# ProProject__CW32__2024-03-17.net
KiCad netlist of a schematic drawn in EasyEDA Pro
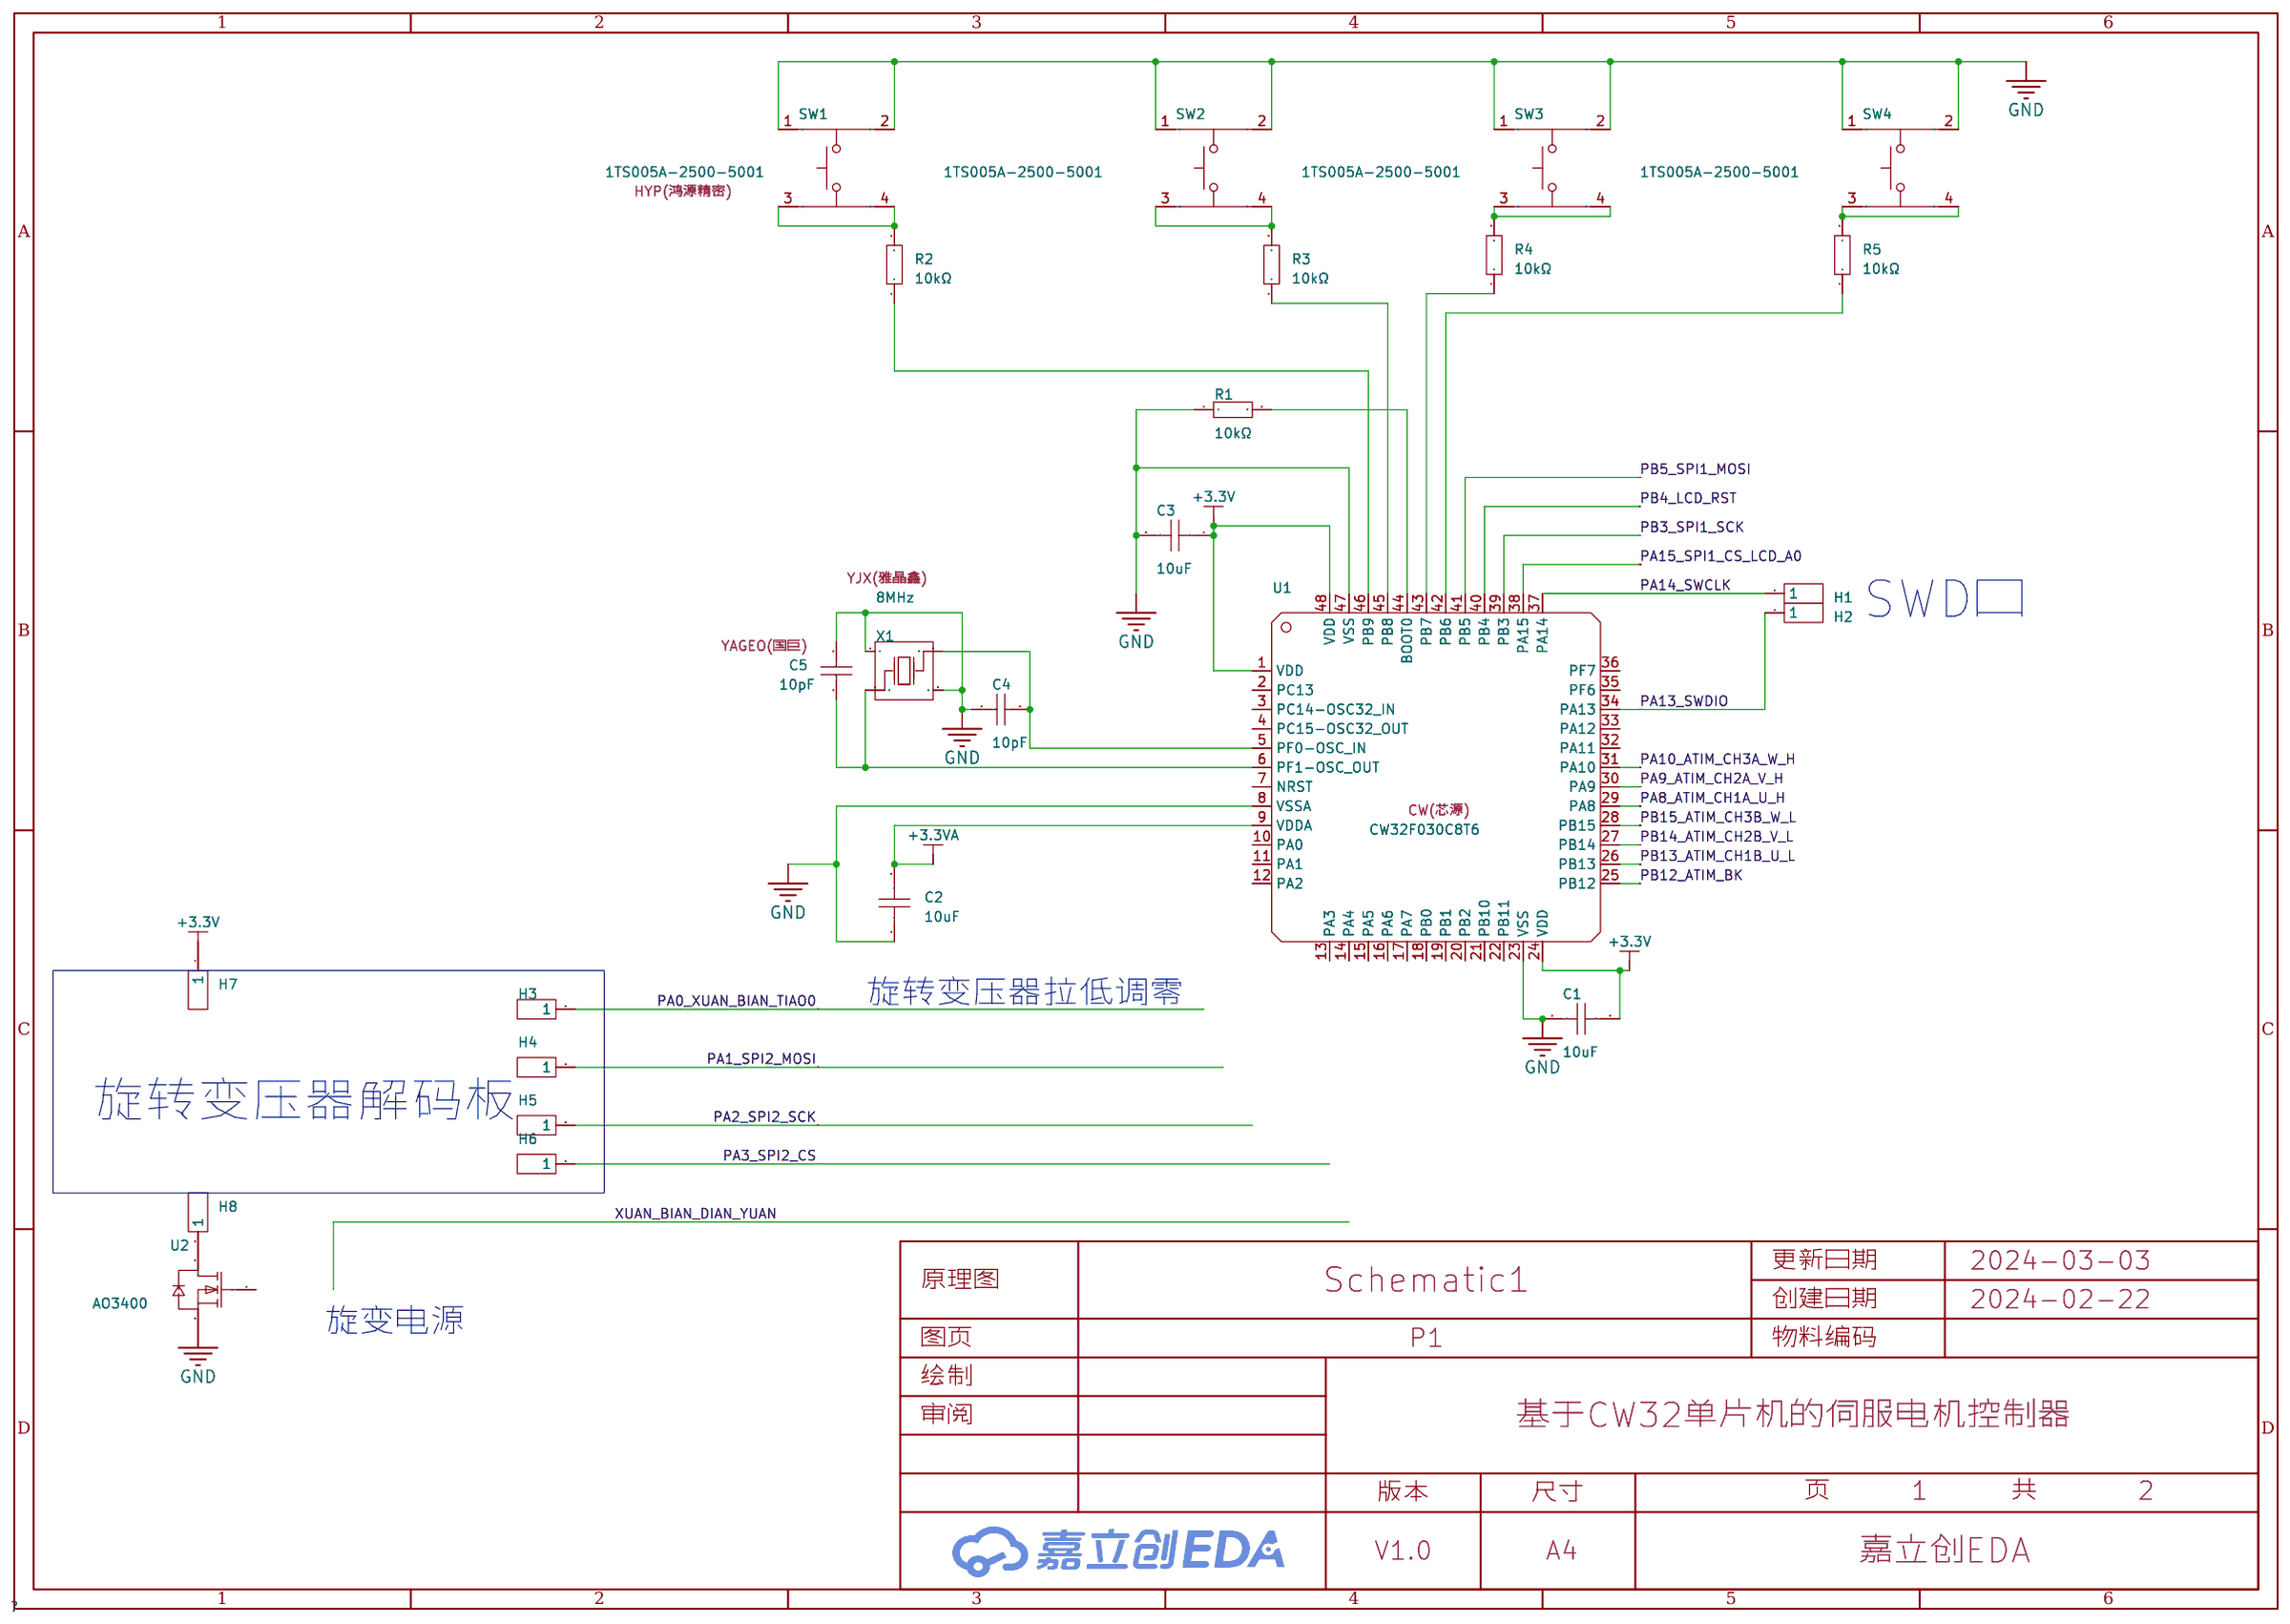
[diagram p0: P1]
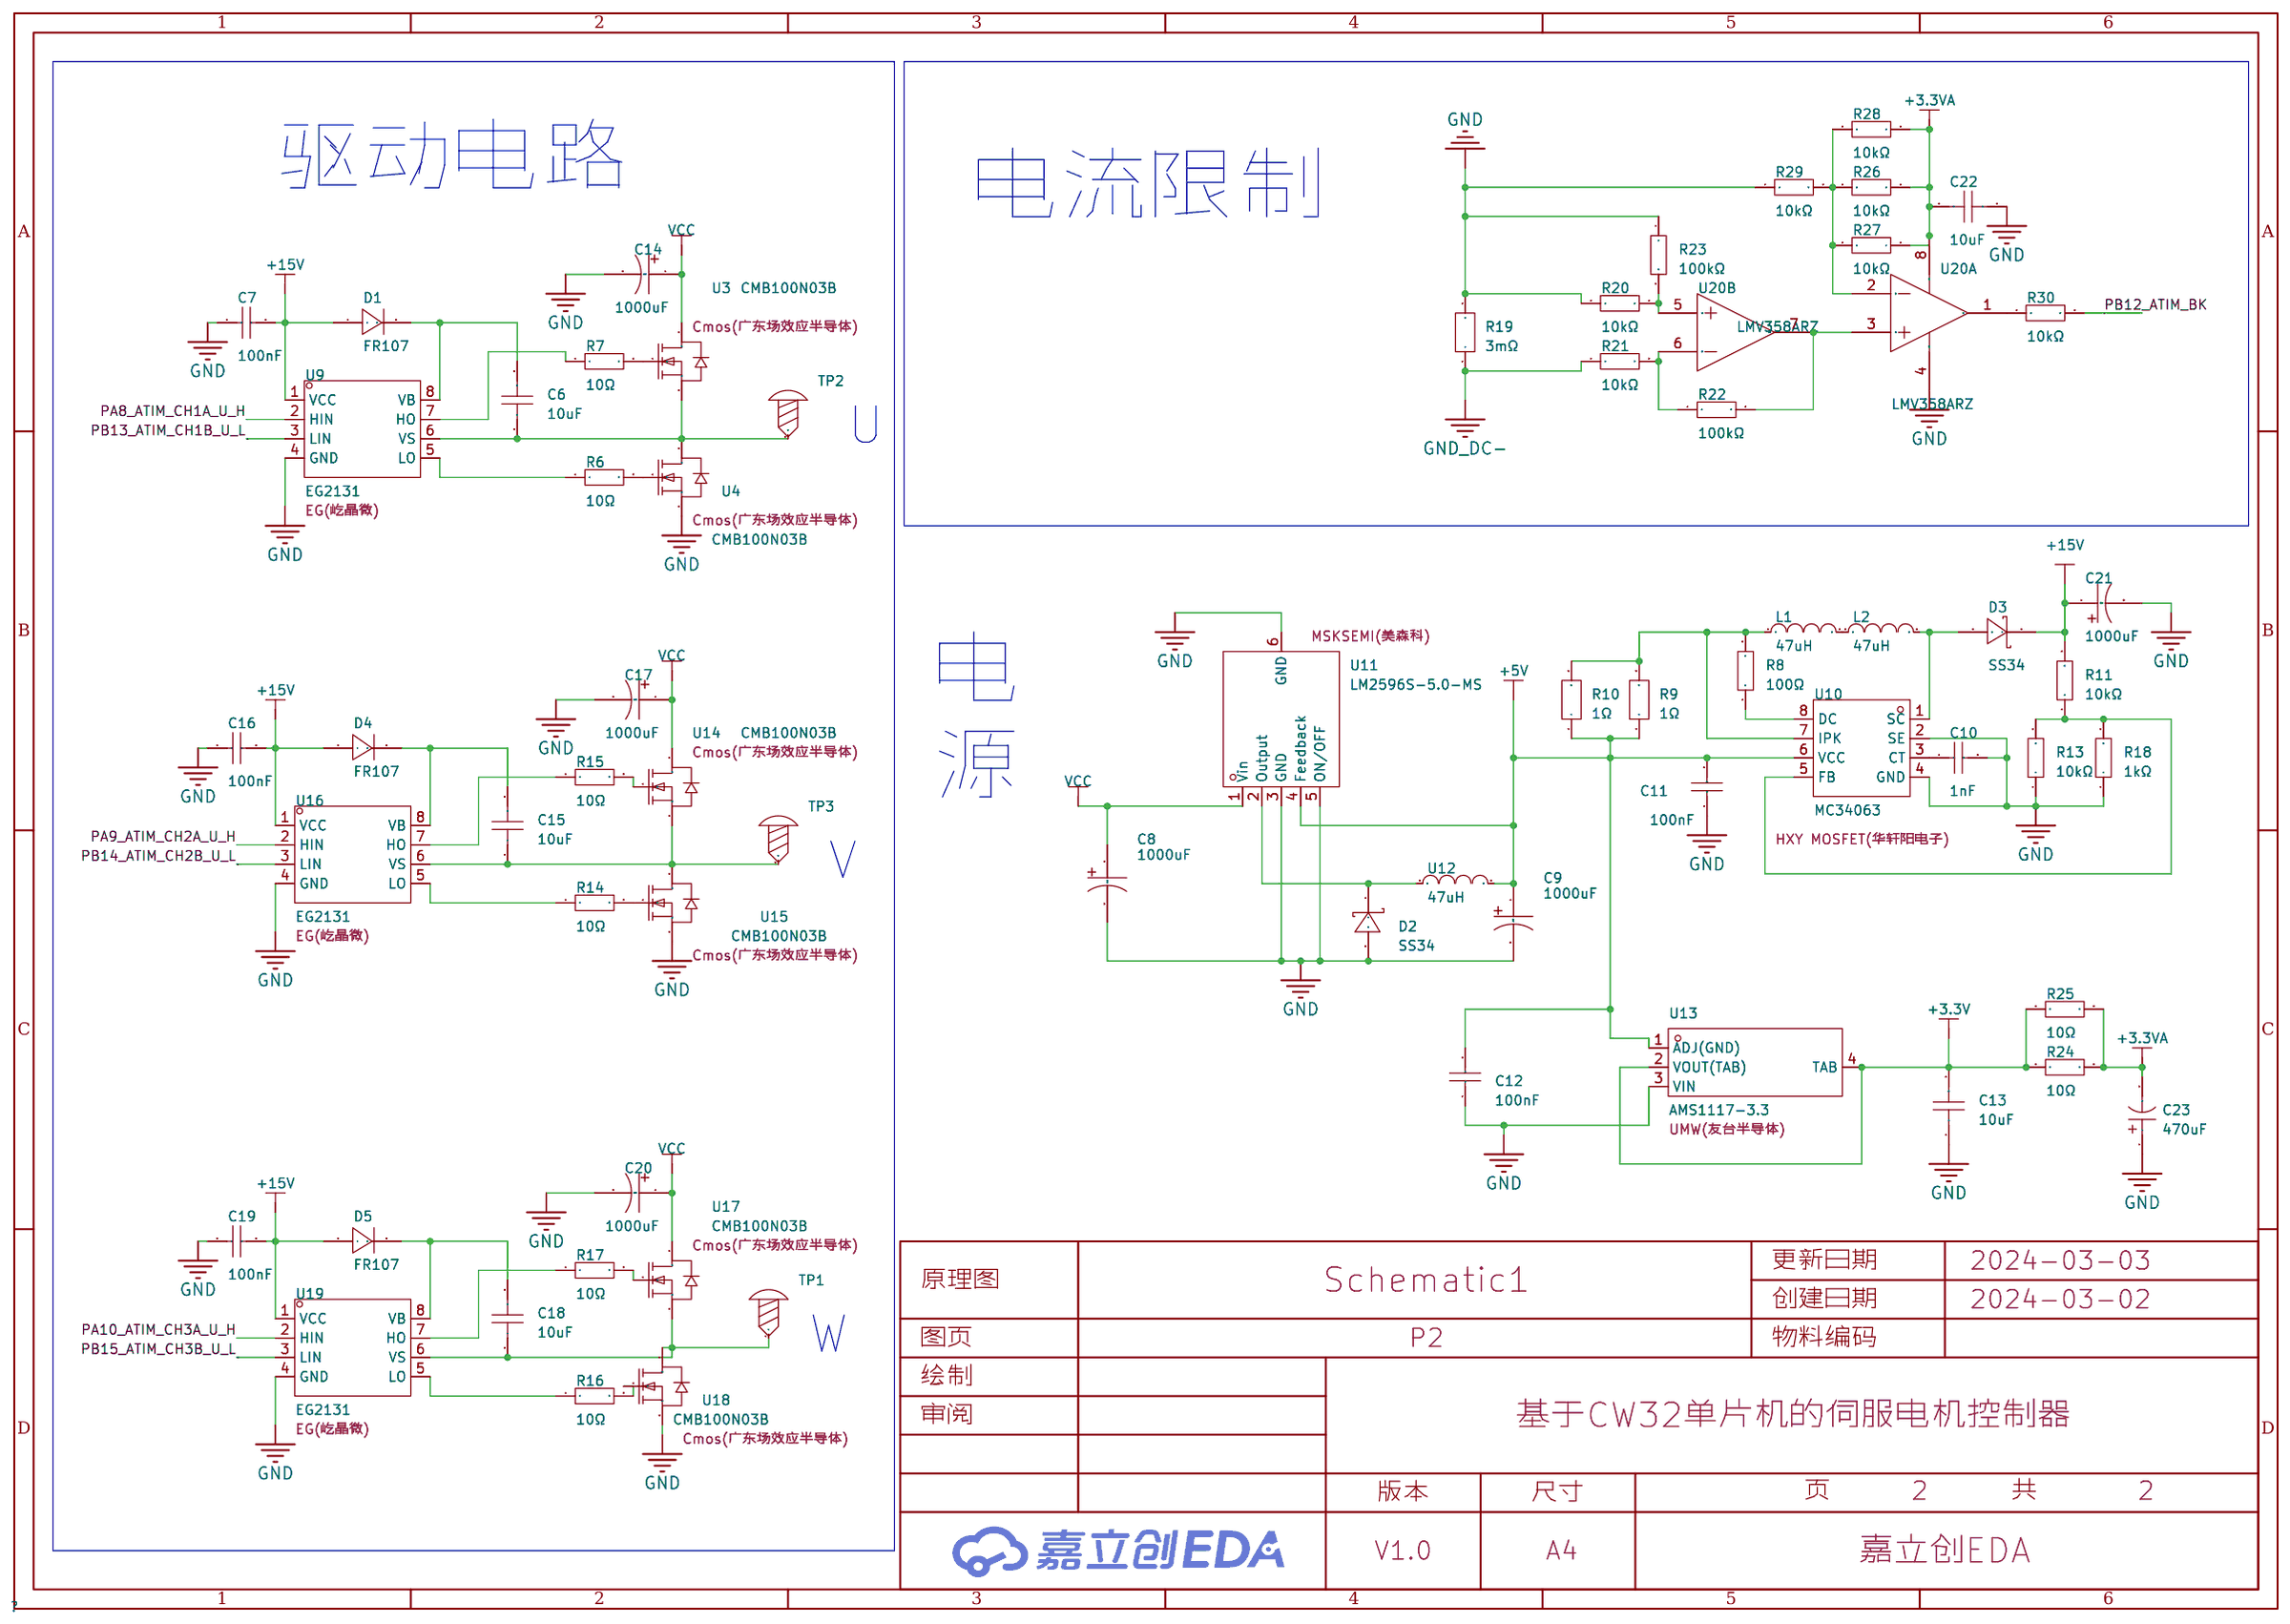
[diagram p1: P2]

(export (version "E")
  (design (tool "Eeschema 10.0.6"))
  (components
    (comp (ref "C1")
      (value "10uF")
      (footprint "easyedapro:C0603")
      (description "容值:10uF;精度:±10%;额定电压:10V;材质(温度系数):X5R;")
      (fields
        (field (name "Manufacturer Part") "CL10A106KP8NNNC")
        (field (name "Manufacturer") "SAMSUNG(三星)")
      )
      (libsource (lib "easyedapro") (part "CL10A106KP8NNNC"))
    )
    (comp (ref "C2")
      (value "10uF")
      (footprint "easyedapro:C0603")
      (description "容值:10uF;精度:±10%;额定电压:10V;材质(温度系数):X5R;")
      (fields
        (field (name "Manufacturer Part") "CL10A106KP8NNNC")
        (field (name "Manufacturer") "SAMSUNG(三星)")
      )
      (libsource (lib "easyedapro") (part "CL10A106KP8NNNC"))
    )
    (comp (ref "C3")
      (value "10uF")
      (footprint "easyedapro:C0603")
      (description "容值:10uF;精度:±10%;额定电压:10V;材质(温度系数):X5R;")
      (fields
        (field (name "Manufacturer Part") "CL10A106KP8NNNC")
        (field (name "Manufacturer") "SAMSUNG(三星)")
      )
      (libsource (lib "easyedapro") (part "CL10A106KP8NNNC"))
    )
    (comp (ref "C4")
      (value "10pF")
      (footprint "easyedapro:C0603")
      (description "容值:10pF;精度:±5%;额定电压:50V;材质(温度系数):NP0;")
      (fields
        (field (name "Manufacturer Part") "CC0603JRNPO9BN100")
        (field (name "Manufacturer") "YAGEO(国巨)")
      )
      (libsource (lib "easyedapro") (part "CC0603JRNPO9BN100"))
    )
    (comp (ref "C5")
      (value "10pF")
      (footprint "easyedapro:C0603")
      (description "容值:10pF;精度:±5%;额定电压:50V;材质(温度系数):NP0;")
      (fields
        (field (name "Manufacturer Part") "CC0603JRNPO9BN100")
        (field (name "Manufacturer") "YAGEO(国巨)")
      )
      (libsource (lib "easyedapro") (part "CC0603JRNPO9BN100"))
    )
    (comp (ref "H1")
      (value "~")
      (footprint "easyedapro:HDR-TH_1P-V-M_XKB_X4611WV-01I-C28D40")
      (libsource (lib "easyedapro") (part "HDR_1x1"))
    )
    (comp (ref "H2")
      (value "~")
      (footprint "easyedapro:HDR-TH_1P-V-M_XKB_X4611WV-01I-C28D40")
      (libsource (lib "easyedapro") (part "HDR_1x1"))
    )
    (comp (ref "H3")
      (value "~")
      (footprint "easyedapro:HDR-TH_1P-V-M_XKB_X4611WV-01I-C28D40")
      (libsource (lib "easyedapro") (part "HDR_1x1"))
    )
    (comp (ref "H4")
      (value "~")
      (footprint "easyedapro:HDR-TH_1P-V-M_XKB_X4611WV-01I-C28D40")
      (libsource (lib "easyedapro") (part "HDR_1x1"))
    )
    (comp (ref "H5")
      (value "~")
      (footprint "easyedapro:HDR-TH_1P-V-M_XKB_X4611WV-01I-C28D40")
      (libsource (lib "easyedapro") (part "HDR_1x1"))
    )
    (comp (ref "H6")
      (value "~")
      (footprint "easyedapro:HDR-TH_1P-V-M_XKB_X4611WV-01I-C28D40")
      (libsource (lib "easyedapro") (part "HDR_1x1"))
    )
    (comp (ref "H7")
      (value "~")
      (footprint "easyedapro:HDR-TH_1P-V-M_XKB_X4611WV-01I-C28D40")
      (libsource (lib "easyedapro") (part "HDR_1x1"))
    )
    (comp (ref "H8")
      (value "~")
      (footprint "easyedapro:HDR-TH_1P-V-M_XKB_X4611WV-01I-C28D40")
      (libsource (lib "easyedapro") (part "HDR_1x1"))
    )
    (comp (ref "R1")
      (value "10kΩ")
      (footprint "easyedapro:R0603")
      (description "电阻类型:厚膜电阻;阻值:10kΩ;精度:±1%;功率:100mW;最大工作电压:75V;温度系数:±100ppm/°C;")
      (fields (field (name "Manufacturer Part") "RC0603FR-0710KL") (field (name "Manufacturer") "YAGEO(国巨)"))
      (libsource (lib "easyedapro") (part "RC0603FR-0710KL"))
    )
    (comp (ref "R2")
      (value "10kΩ")
      (footprint "easyedapro:R0603")
      (description "电阻类型:厚膜电阻;阻值:10kΩ;精度:±1%;功率:100mW;最大工作电压:75V;温度系数:±100ppm/°C;")
      (fields (field (name "Manufacturer Part") "RC0603FR-0710KL") (field (name "Manufacturer") "YAGEO(国巨)"))
      (libsource (lib "easyedapro") (part "RC0603FR-0710KL"))
    )
    (comp (ref "R3")
      (value "10kΩ")
      (footprint "easyedapro:R0603")
      (description "电阻类型:厚膜电阻;阻值:10kΩ;精度:±1%;功率:100mW;最大工作电压:75V;温度系数:±100ppm/°C;")
      (fields (field (name "Manufacturer Part") "RC0603FR-0710KL") (field (name "Manufacturer") "YAGEO(国巨)"))
      (libsource (lib "easyedapro") (part "RC0603FR-0710KL"))
    )
    (comp (ref "R4")
      (value "10kΩ")
      (footprint "easyedapro:R0603")
      (description "电阻类型:厚膜电阻;阻值:10kΩ;精度:±1%;功率:100mW;最大工作电压:75V;温度系数:±100ppm/°C;")
      (fields (field (name "Manufacturer Part") "RC0603FR-0710KL") (field (name "Manufacturer") "YAGEO(国巨)"))
      (libsource (lib "easyedapro") (part "RC0603FR-0710KL"))
    )
    (comp (ref "R5")
      (value "10kΩ")
      (footprint "easyedapro:R0603")
      (description "电阻类型:厚膜电阻;阻值:10kΩ;精度:±1%;功率:100mW;最大工作电压:75V;温度系数:±100ppm/°C;")
      (fields (field (name "Manufacturer Part") "RC0603FR-0710KL") (field (name "Manufacturer") "YAGEO(国巨)"))
      (libsource (lib "easyedapro") (part "RC0603FR-0710KL"))
    )
    (comp (ref "SW1")
      (value "1TS005A-2500-5001")
      (footprint "easyedapro:SW-TH_4P-L6.0-W6.0-P3.90-LS6.5")
      (fields (field (name "Manufacturer") "HYP(鸿源精密)"))
      (libsource (lib "easyedapro") (part "1TS005A-2500-5001"))
    )
    (comp (ref "SW2")
      (value "1TS005A-2500-5001")
      (footprint "easyedapro:SW-TH_4P-L6.0-W6.0-P3.90-LS6.5")
      (fields (field (name "Manufacturer") "HYP(鸿源精密)"))
      (libsource (lib "easyedapro") (part "1TS005A-2500-5001"))
    )
    (comp (ref "SW3")
      (value "1TS005A-2500-5001")
      (footprint "easyedapro:SW-TH_4P-L6.0-W6.0-P3.90-LS6.5")
      (fields (field (name "Manufacturer") "HYP(鸿源精密)"))
      (libsource (lib "easyedapro") (part "1TS005A-2500-5001"))
    )
    (comp (ref "SW4")
      (value "1TS005A-2500-5001")
      (footprint "easyedapro:SW-TH_4P-L6.0-W6.0-P3.90-LS6.5")
      (fields (field (name "Manufacturer") "HYP(鸿源精密)"))
      (libsource (lib "easyedapro") (part "1TS005A-2500-5001"))
    )
    (comp (ref "U1")
      (value "CW32F030C8T6")
      (footprint "easyedapro:LQFP-48_L7.0-W7.0-P0.50-LS9.0-TL")
      (description "CPU内核:ARM-M系列;RAM总容量:8KB;GPIO端口数量:39;工作电压范围:1.65V~5.5V;CPU最大主频:64MHz;程序存储器类型:-;")
      (fields (field (name "Manufacturer") "CW(芯源)"))
      (libsource (lib "easyedapro") (part "CW32F030C8T6_C3019113"))
    )
    (comp (ref "U2")
      (value "AO3400")
      (footprint "easyedapro:SOT-23-3_L2.9-W1.3-P0.95-LS2.4-BR")
      (fields (field (name "Manufacturer") "ElecSuper(静芯微)"))
      (libsource (lib "easyedapro") (part "AO3400_C5224189"))
    )
    (comp (ref "X1")
      (value "8MHz")
      (footprint "easyedapro:OSC-SMD_4P-L3.2-W2.5-BL")
      (description "晶振类型:贴片晶振;频率:8MHz;常温频差:±10ppm;外接负载电容:10pF;频率稳定度(全温):±15ppm;")
      (fields (field (name "Manufacturer Part") "TAXM8M4RDBCCT2T") (field (name "Manufacturer") "YJX(雅晶鑫)"))
      (libsource (lib "easyedapro") (part "TAXM8M4RDBCCT2T"))
    )
    (comp (ref "C6")
      (value "10uF")
      (footprint "easyedapro:C0805")
      (description "容值:10uF;精度:±10%;额定电压:25V;材质(温度系数):X5R;")
      (fields
        (field (name "Manufacturer Part") "CL21A106KAYNNNE")
        (field (name "Manufacturer") "SAMSUNG(三星)")
      )
      (libsource (lib "easyedapro") (part "CL21A106KAYNNNE"))
    )
    (comp (ref "C7")
      (value "100nF")
      (footprint "easyedapro:C0603")
      (description "容值:100nF;精度:±10%;额定电压:50V;材质(温度系数):X7R;")
      (fields (field (name "Manufacturer Part") "0603B104K500NT") (field (name "Manufacturer") "FH(风华)"))
      (libsource (lib "easyedapro") (part "0603B104K500NT"))
    )
    (comp (ref "C8")
      (value "1000uF")
      (footprint "easyedapro:CAP-TH_BD10.0-P5.00-D1.0-FD")
      (description "容值:1000uF;精度:±20%;额定电压:35V;")
      (fields (field (name "Manufacturer Part") "ERR1VM102G20OT") (field (name "Manufacturer") "AISHI(艾华集团)"))
      (libsource (lib "easyedapro") (part "ERR1VM102G20OT"))
    )
    (comp (ref "C9")
      (value "1000uF")
      (footprint "easyedapro:CAP-TH_BD10.0-P5.00-D1.0-FD")
      (description "容值:1000uF;精度:±20%;额定电压:35V;")
      (fields (field (name "Manufacturer Part") "ERR1VM102G20OT") (field (name "Manufacturer") "AISHI(艾华集团)"))
      (libsource (lib "easyedapro") (part "ERR1VM102G20OT"))
    )
    (comp (ref "C10")
      (value "1nF")
      (footprint "easyedapro:C0603")
      (description "容值:1nF;精度:±5%;额定电压:50V;材质(温度系数):NP0;")
      (fields
        (field (name "Manufacturer Part") "CC0603JRNPO9BN102")
        (field (name "Manufacturer") "YAGEO(国巨)")
      )
      (libsource (lib "easyedapro") (part "CC0603JRNPO9BN102"))
    )
    (comp (ref "C11")
      (value "100nF")
      (footprint "easyedapro:C0603")
      (description "容值:100nF;精度:±10%;额定电压:50V;材质(温度系数):X7R;")
      (fields (field (name "Manufacturer Part") "0603B104K500NT") (field (name "Manufacturer") "FH(风华)"))
      (libsource (lib "easyedapro") (part "0603B104K500NT"))
    )
    (comp (ref "C12")
      (value "100nF")
      (footprint "easyedapro:C0603")
      (description "容值:100nF;精度:±10%;额定电压:50V;材质(温度系数):X7R;")
      (fields (field (name "Manufacturer Part") "0603B104K500NT") (field (name "Manufacturer") "FH(风华)"))
      (libsource (lib "easyedapro") (part "0603B104K500NT"))
    )
    (comp (ref "C13")
      (value "10uF")
      (footprint "easyedapro:C0603")
      (description "容值:10uF;精度:±10%;额定电压:10V;材质(温度系数):X5R;")
      (fields
        (field (name "Manufacturer Part") "CL10A106KP8NNNC")
        (field (name "Manufacturer") "SAMSUNG(三星)")
      )
      (libsource (lib "easyedapro") (part "CL10A106KP8NNNC"))
    )
    (comp (ref "C14")
      (value "1000uF")
      (footprint "easyedapro:CAP-TH_BD10.0-P5.00-D1.0-FD")
      (description "容值:1000uF;精度:±20%;额定电压:35V;")
      (fields (field (name "Manufacturer Part") "ERR1VM102G20OT") (field (name "Manufacturer") "AISHI(艾华集团)"))
      (libsource (lib "easyedapro") (part "ERR1VM102G20OT"))
    )
    (comp (ref "C15")
      (value "10uF")
      (footprint "easyedapro:C0805")
      (description "容值:10uF;精度:±10%;额定电压:25V;材质(温度系数):X5R;")
      (fields
        (field (name "Manufacturer Part") "CL21A106KAYNNNE")
        (field (name "Manufacturer") "SAMSUNG(三星)")
      )
      (libsource (lib "easyedapro") (part "CL21A106KAYNNNE"))
    )
    (comp (ref "C16")
      (value "100nF")
      (footprint "easyedapro:C0603")
      (description "容值:100nF;精度:±10%;额定电压:50V;材质(温度系数):X7R;")
      (fields (field (name "Manufacturer Part") "0603B104K500NT") (field (name "Manufacturer") "FH(风华)"))
      (libsource (lib "easyedapro") (part "0603B104K500NT"))
    )
    (comp (ref "C17")
      (value "1000uF")
      (footprint "easyedapro:CAP-TH_BD10.0-P5.00-D1.0-FD")
      (description "容值:1000uF;精度:±20%;额定电压:35V;")
      (fields (field (name "Manufacturer Part") "ERR1VM102G20OT") (field (name "Manufacturer") "AISHI(艾华集团)"))
      (libsource (lib "easyedapro") (part "ERR1VM102G20OT"))
    )
    (comp (ref "C18")
      (value "10uF")
      (footprint "easyedapro:C0805")
      (description "容值:10uF;精度:±10%;额定电压:25V;材质(温度系数):X5R;")
      (fields
        (field (name "Manufacturer Part") "CL21A106KAYNNNE")
        (field (name "Manufacturer") "SAMSUNG(三星)")
      )
      (libsource (lib "easyedapro") (part "CL21A106KAYNNNE"))
    )
    (comp (ref "C19")
      (value "100nF")
      (footprint "easyedapro:C0603")
      (description "容值:100nF;精度:±10%;额定电压:50V;材质(温度系数):X7R;")
      (fields (field (name "Manufacturer Part") "0603B104K500NT") (field (name "Manufacturer") "FH(风华)"))
      (libsource (lib "easyedapro") (part "0603B104K500NT"))
    )
    (comp (ref "C20")
      (value "1000uF")
      (footprint "easyedapro:CAP-TH_BD10.0-P5.00-D1.0-FD")
      (description "容值:1000uF;精度:±20%;额定电压:35V;")
      (fields (field (name "Manufacturer Part") "ERR1VM102G20OT") (field (name "Manufacturer") "AISHI(艾华集团)"))
      (libsource (lib "easyedapro") (part "ERR1VM102G20OT"))
    )
    (comp (ref "C21")
      (value "1000uF")
      (footprint "easyedapro:CAP-TH_BD10.0-P5.00-D1.0-FD")
      (description "容值:1000uF;精度:±20%;额定电压:35V;")
      (fields (field (name "Manufacturer Part") "ERR1VM102G20OT") (field (name "Manufacturer") "AISHI(艾华集团)"))
      (libsource (lib "easyedapro") (part "ERR1VM102G20OT"))
    )
    (comp (ref "C22")
      (value "10uF")
      (footprint "easyedapro:C0603")
      (description "容值:10uF;精度:±10%;额定电压:10V;材质(温度系数):X5R;")
      (fields
        (field (name "Manufacturer Part") "CL10A106KP8NNNC")
        (field (name "Manufacturer") "SAMSUNG(三星)")
      )
      (libsource (lib "easyedapro") (part "CL10A106KP8NNNC"))
    )
    (comp (ref "C23")
      (value "470uF")
      (footprint "easyedapro:CAP-TH_BD10.0-P5.00-D0.6-FD")
      (description "容值:470uF;精度:±20%;额定电压:35V;")
      (fields (field (name "Manufacturer Part") "35V470uF CD110") (field (name "Manufacturer") "HRK(鸿瑞凯电子)"))
      (libsource (lib "easyedapro") (part "35V470UF CD110"))
    )
    (comp (ref "D1")
      (value "FR107")
      (footprint "easyedapro:DO-41_BD2.4-L4.7-P8.70-D0.9-FD")
      (description "二极管配置:-;正向压降(Vf):1.3V@1A;直流反向耐压(Vr):1kV;平均整流电流(Io):1A;反向恢复时间(trr):500ns;")
      (fields (field (name "Manufacturer") "MDD"))
      (libsource (lib "easyedapro") (part "FR107_C35253"))
    )
    (comp (ref "D2")
      (value "SS34")
      (footprint "easyedapro:SMA_L4.3-W2.6-LS5.2-RD")
      (description "二极管配置:独立式;正向压降(Vf):550mV@3A;直流反向耐压(Vr):40V;平均整流电流(Io):3A;")
      (fields (field (name "Manufacturer") "MDD"))
      (libsource (lib "easyedapro") (part "SS34_C8678"))
    )
    (comp (ref "D3")
      (value "SS34")
      (footprint "easyedapro:SMA_L4.3-W2.6-LS5.2-RD")
      (description "二极管配置:独立式;正向压降(Vf):550mV@3A;直流反向耐压(Vr):40V;平均整流电流(Io):3A;")
      (fields (field (name "Manufacturer") "MDD"))
      (libsource (lib "easyedapro") (part "SS34_C8678"))
    )
    (comp (ref "D4")
      (value "FR107")
      (footprint "easyedapro:DO-41_BD2.4-L4.7-P8.70-D0.9-FD")
      (description "二极管配置:-;正向压降(Vf):1.3V@1A;直流反向耐压(Vr):1kV;平均整流电流(Io):1A;反向恢复时间(trr):500ns;")
      (fields (field (name "Manufacturer") "MDD"))
      (libsource (lib "easyedapro") (part "FR107_C35253"))
    )
    (comp (ref "D5")
      (value "FR107")
      (footprint "easyedapro:DO-41_BD2.4-L4.7-P8.70-D0.9-FD")
      (description "二极管配置:-;正向压降(Vf):1.3V@1A;直流反向耐压(Vr):1kV;平均整流电流(Io):1A;反向恢复时间(trr):500ns;")
      (fields (field (name "Manufacturer") "MDD"))
      (libsource (lib "easyedapro") (part "FR107_C35253"))
    )
    (comp (ref "L1")
      (value "47uH")
      (footprint "easyedapro:IND-SMD_L4.5-W4.0_SLF0403")
      (description "电感值:47uH;精度:±10%;额定电流:540mA;")
      (fields
        (field (name "Manufacturer Part") "SLF0403-470KTT")
        (field (name "Manufacturer") "Sunltech(韩国顺磁)")
      )
      (libsource (lib "easyedapro") (part "SLF0403-470KTT"))
    )
    (comp (ref "L2")
      (value "47uH")
      (footprint "easyedapro:IND-SMD_L4.5-W4.0_SLF0403")
      (description "电感值:47uH;精度:±10%;额定电流:540mA;")
      (fields
        (field (name "Manufacturer Part") "SLF0403-470KTT")
        (field (name "Manufacturer") "Sunltech(韩国顺磁)")
      )
      (libsource (lib "easyedapro") (part "SLF0403-470KTT"))
    )
    (comp (ref "R6")
      (value "10Ω")
      (footprint "easyedapro:R0603")
      (description "电阻类型:厚膜电阻;阻值:10Ω;精度:±1%;功率:100mW;最大工作电压:75V;温度系数:±400ppm/°C;")
      (fields
        (field (name "Manufacturer Part") "0603WAF100JT5E")
        (field (name "Manufacturer") "UNI-ROYAL(厚声)")
      )
      (libsource (lib "easyedapro") (part "0603WAF100JT5E"))
    )
    (comp (ref "R7")
      (value "10Ω")
      (footprint "easyedapro:R0603")
      (description "电阻类型:厚膜电阻;阻值:10Ω;精度:±1%;功率:100mW;最大工作电压:75V;温度系数:±400ppm/°C;")
      (fields
        (field (name "Manufacturer Part") "0603WAF100JT5E")
        (field (name "Manufacturer") "UNI-ROYAL(厚声)")
      )
      (libsource (lib "easyedapro") (part "0603WAF100JT5E"))
    )
    (comp (ref "R8")
      (value "100Ω")
      (footprint "easyedapro:R0603")
      (description "电阻类型:厚膜电阻;阻值:100Ω;精度:±1%;功率:100mW;最大工作电压:75V;温度系数:±100ppm/°C;")
      (fields (field (name "Manufacturer Part") "RC0603FR-07100RL") (field (name "Manufacturer") "YAGEO(国巨)"))
      (libsource (lib "easyedapro") (part "RC0603FR-07100RL"))
    )
    (comp (ref "R9")
      (value "1Ω")
      (footprint "easyedapro:R0603")
      (description "电阻类型:厚膜电阻;阻值:1Ω;精度:±1%;功率:100mW;最大工作电压:75V;")
      (fields (field (name "Manufacturer Part") "SCR0603F1R") (field (name "Manufacturer") "VO(翔胜)"))
      (libsource (lib "easyedapro") (part "SCR0603F1R"))
    )
    (comp (ref "R10")
      (value "1Ω")
      (footprint "easyedapro:R0603")
      (description "电阻类型:厚膜电阻;阻值:1Ω;精度:±1%;功率:100mW;最大工作电压:75V;")
      (fields (field (name "Manufacturer Part") "SCR0603F1R") (field (name "Manufacturer") "VO(翔胜)"))
      (libsource (lib "easyedapro") (part "SCR0603F1R"))
    )
    (comp (ref "R11")
      (value "10kΩ")
      (footprint "easyedapro:R0603")
      (description "电阻类型:厚膜电阻;阻值:10kΩ;精度:±1%;功率:100mW;最大工作电压:75V;温度系数:±100ppm/°C;")
      (fields (field (name "Manufacturer Part") "RC0603FR-0710KL") (field (name "Manufacturer") "YAGEO(国巨)"))
      (libsource (lib "easyedapro") (part "RC0603FR-0710KL"))
    )
    (comp (ref "R13")
      (value "10kΩ")
      (footprint "easyedapro:R0603")
      (description "电阻类型:厚膜电阻;阻值:10kΩ;精度:±1%;功率:100mW;最大工作电压:75V;温度系数:±100ppm/°C;")
      (fields (field (name "Manufacturer Part") "RC0603FR-0710KL") (field (name "Manufacturer") "YAGEO(国巨)"))
      (libsource (lib "easyedapro") (part "RC0603FR-0710KL"))
    )
    (comp (ref "R14")
      (value "10Ω")
      (footprint "easyedapro:R0603")
      (description "电阻类型:厚膜电阻;阻值:10Ω;精度:±1%;功率:100mW;最大工作电压:75V;温度系数:±400ppm/°C;")
      (fields
        (field (name "Manufacturer Part") "0603WAF100JT5E")
        (field (name "Manufacturer") "UNI-ROYAL(厚声)")
      )
      (libsource (lib "easyedapro") (part "0603WAF100JT5E"))
    )
    (comp (ref "R15")
      (value "10Ω")
      (footprint "easyedapro:R0603")
      (description "电阻类型:厚膜电阻;阻值:10Ω;精度:±1%;功率:100mW;最大工作电压:75V;温度系数:±400ppm/°C;")
      (fields
        (field (name "Manufacturer Part") "0603WAF100JT5E")
        (field (name "Manufacturer") "UNI-ROYAL(厚声)")
      )
      (libsource (lib "easyedapro") (part "0603WAF100JT5E"))
    )
    (comp (ref "R16")
      (value "10Ω")
      (footprint "easyedapro:R0603")
      (description "电阻类型:厚膜电阻;阻值:10Ω;精度:±1%;功率:100mW;最大工作电压:75V;温度系数:±400ppm/°C;")
      (fields
        (field (name "Manufacturer Part") "0603WAF100JT5E")
        (field (name "Manufacturer") "UNI-ROYAL(厚声)")
      )
      (libsource (lib "easyedapro") (part "0603WAF100JT5E"))
    )
    (comp (ref "R17")
      (value "10Ω")
      (footprint "easyedapro:R0603")
      (description "电阻类型:厚膜电阻;阻值:10Ω;精度:±1%;功率:100mW;最大工作电压:75V;温度系数:±400ppm/°C;")
      (fields
        (field (name "Manufacturer Part") "0603WAF100JT5E")
        (field (name "Manufacturer") "UNI-ROYAL(厚声)")
      )
      (libsource (lib "easyedapro") (part "0603WAF100JT5E"))
    )
    (comp (ref "R18")
      (value "1kΩ")
      (footprint "easyedapro:R0603")
      (description "电阻类型:厚膜电阻;阻值:1kΩ;精度:±1%;功率:100mW;最大工作电压:75V;温度系数:±100ppm/°C;")
      (fields (field (name "Manufacturer Part") "RC0603FR-071KL") (field (name "Manufacturer") "YAGEO(国巨)"))
      (libsource (lib "easyedapro") (part "RC0603FR-071KL"))
    )
    (comp (ref "R19")
      (value "3mΩ")
      (footprint "easyedapro:R5930")
      (description "电阻类型:采样电阻;阻值:3mΩ;精度:±1%;额定压降:-;功率:7W;温度系数:±100ppm/°C;安装方式:贴片;")
      (fields
        (field (name "Manufacturer Part") "EBWS5930F3L00K9L")
        (field (name "Manufacturer") "RESI(开步睿思）")
      )
      (libsource (lib "easyedapro") (part "EBWS5930F3L00K9L"))
    )
    (comp (ref "R20")
      (value "10kΩ")
      (footprint "easyedapro:R0603")
      (description "电阻类型:厚膜电阻;阻值:10kΩ;精度:±1%;功率:100mW;最大工作电压:75V;温度系数:±100ppm/°C;")
      (fields (field (name "Manufacturer Part") "RC0603FR-0710KL") (field (name "Manufacturer") "YAGEO(国巨)"))
      (libsource (lib "easyedapro") (part "RC0603FR-0710KL"))
    )
    (comp (ref "R21")
      (value "10kΩ")
      (footprint "easyedapro:R0603")
      (description "电阻类型:厚膜电阻;阻值:10kΩ;精度:±1%;功率:100mW;最大工作电压:75V;温度系数:±100ppm/°C;")
      (fields (field (name "Manufacturer Part") "RC0603FR-0710KL") (field (name "Manufacturer") "YAGEO(国巨)"))
      (libsource (lib "easyedapro") (part "RC0603FR-0710KL"))
    )
    (comp (ref "R22")
      (value "100kΩ")
      (footprint "easyedapro:R0603")
      (description "电阻类型:厚膜电阻;阻值:100kΩ;精度:±1%;功率:100mW;最大工作电压:75V;温度系数:±100ppm/°C;")
      (fields (field (name "Manufacturer Part") "RC0603FR-07100KL") (field (name "Manufacturer") "YAGEO(国巨)"))
      (libsource (lib "easyedapro") (part "RC0603FR-07100KL"))
    )
    (comp (ref "R23")
      (value "100kΩ")
      (footprint "easyedapro:R0603")
      (description "电阻类型:厚膜电阻;阻值:100kΩ;精度:±1%;功率:100mW;最大工作电压:75V;温度系数:±100ppm/°C;")
      (fields (field (name "Manufacturer Part") "RC0603FR-07100KL") (field (name "Manufacturer") "YAGEO(国巨)"))
      (libsource (lib "easyedapro") (part "RC0603FR-07100KL"))
    )
    (comp (ref "R24")
      (value "10Ω")
      (footprint "easyedapro:R0603")
      (description "电阻类型:厚膜电阻;阻值:10Ω;精度:±1%;功率:100mW;最大工作电压:75V;温度系数:±400ppm/°C;")
      (fields
        (field (name "Manufacturer Part") "0603WAF100JT5E")
        (field (name "Manufacturer") "UNI-ROYAL(厚声)")
      )
      (libsource (lib "easyedapro") (part "0603WAF100JT5E"))
    )
    (comp (ref "R25")
      (value "10Ω")
      (footprint "easyedapro:R0603")
      (description "电阻类型:厚膜电阻;阻值:10Ω;精度:±1%;功率:100mW;最大工作电压:75V;温度系数:±400ppm/°C;")
      (fields
        (field (name "Manufacturer Part") "0603WAF100JT5E")
        (field (name "Manufacturer") "UNI-ROYAL(厚声)")
      )
      (libsource (lib "easyedapro") (part "0603WAF100JT5E"))
    )
    (comp (ref "R26")
      (value "10kΩ")
      (footprint "easyedapro:R0603")
      (description "电阻类型:厚膜电阻;阻值:10kΩ;精度:±1%;功率:100mW;最大工作电压:75V;温度系数:±100ppm/°C;")
      (fields (field (name "Manufacturer Part") "RC0603FR-0710KL") (field (name "Manufacturer") "YAGEO(国巨)"))
      (libsource (lib "easyedapro") (part "RC0603FR-0710KL"))
    )
    (comp (ref "R27")
      (value "10kΩ")
      (footprint "easyedapro:R0603")
      (description "电阻类型:厚膜电阻;阻值:10kΩ;精度:±1%;功率:100mW;最大工作电压:75V;温度系数:±100ppm/°C;")
      (fields (field (name "Manufacturer Part") "RC0603FR-0710KL") (field (name "Manufacturer") "YAGEO(国巨)"))
      (libsource (lib "easyedapro") (part "RC0603FR-0710KL"))
    )
    (comp (ref "R28")
      (value "10kΩ")
      (footprint "easyedapro:R0603")
      (description "电阻类型:厚膜电阻;阻值:10kΩ;精度:±1%;功率:100mW;最大工作电压:75V;温度系数:±100ppm/°C;")
      (fields (field (name "Manufacturer Part") "RC0603FR-0710KL") (field (name "Manufacturer") "YAGEO(国巨)"))
      (libsource (lib "easyedapro") (part "RC0603FR-0710KL"))
    )
    (comp (ref "R29")
      (value "10kΩ")
      (footprint "easyedapro:R0603")
      (description "电阻类型:厚膜电阻;阻值:10kΩ;精度:±1%;功率:100mW;最大工作电压:75V;温度系数:±100ppm/°C;")
      (fields (field (name "Manufacturer Part") "RC0603FR-0710KL") (field (name "Manufacturer") "YAGEO(国巨)"))
      (libsource (lib "easyedapro") (part "RC0603FR-0710KL"))
    )
    (comp (ref "R30")
      (value "10kΩ")
      (footprint "easyedapro:R0603")
      (description "电阻类型:厚膜电阻;阻值:10kΩ;精度:±1%;功率:100mW;最大工作电压:75V;温度系数:±100ppm/°C;")
      (fields (field (name "Manufacturer Part") "RC0603FR-0710KL") (field (name "Manufacturer") "YAGEO(国巨)"))
      (libsource (lib "easyedapro") (part "RC0603FR-0710KL"))
    )
    (comp (ref "TP1") (value "~") (footprint "easyedapro:M4螺丝") (libsource (lib "easyedapro") (part "螺丝孔")))
    (comp (ref "TP2") (value "~") (footprint "easyedapro:M4螺丝") (libsource (lib "easyedapro") (part "螺丝孔")))
    (comp (ref "TP3") (value "~") (footprint "easyedapro:M4螺丝") (libsource (lib "easyedapro") (part "螺丝孔")))
    (comp (ref "U3")
      (value "CMB100N03B")
      (footprint "easyedapro:TO-263-2_L10.1-W9.1-P5.08-LS15.2-BR")
      (description "类型:N沟道;漏源电压(Vdss):30V;连续漏极电流(Id):100A;功率(Pd):300W;导通电阻(RDS(on)@Vgs,Id):4.5mΩ;")
      (fields (field (name "Manufacturer") "Cmos(广东场效应半导体)"))
      (libsource (lib "easyedapro") (part "CMB100N03B"))
    )
    (comp (ref "U4")
      (value "CMB100N03B")
      (footprint "easyedapro:TO-263-2_L10.1-W9.1-P5.08-LS15.2-BR")
      (description "类型:N沟道;漏源电压(Vdss):30V;连续漏极电流(Id):100A;功率(Pd):300W;导通电阻(RDS(on)@Vgs,Id):4.5mΩ;")
      (fields (field (name "Manufacturer") "Cmos(广东场效应半导体)"))
      (libsource (lib "easyedapro") (part "CMB100N03B"))
    )
    (comp (ref "U9")
      (value "EG2131")
      (footprint "easyedapro:SOIC-8_L5.0-W4.0-P1.27-LS6.0-BL")
      (fields (field (name "Manufacturer") "EG(屹晶微)"))
      (libsource (lib "easyedapro") (part "EG2131"))
    )
    (comp (ref "U10")
      (value "MC34063")
      (footprint "easyedapro:SOIC-8_L5.0-W4.0-P1.27-LS6.0-BL")
      (description "功能类型:升降压型;输出类型:可调;输入电压:3V~40V;输出电压:1.25V~40V;输出电流(最大值):1.3A;")
      (fields (field (name "Manufacturer") "HXY MOSFET(华轩阳电子)"))
      (libsource (lib "easyedapro") (part "MC34063_C5349988"))
    )
    (comp (ref "U11")
      (value "LM2596S-5.0-MS")
      (footprint "easyedapro:TO-263-5_L10.0-W8.4-P1.70-LS15.3-BR")
      (description "功能类型:降压型;输出类型:-;输入电压:7V~40V;输出电压:5V;输出电流(最大值):3A;")
      (fields (field (name "Manufacturer") "MSKSEMI(美森科)"))
      (libsource (lib "easyedapro") (part "LM2596S-5.0_C5174628"))
    )
    (comp (ref "U12")
      (value "47uH")
      (footprint "easyedapro:IND-SMD_L7.1-W6.6")
      (description "电感值:47uH;精度:±20%;额定电流:1.25A;饱和电流(Isat):1.66A;类型:一体成型电感;")
      (fields (field (name "Manufacturer Part") "APH0630T470M") (field (name "Manufacturer") "APV(爱普微)"))
      (libsource (lib "easyedapro") (part "APH0630T470M"))
    )
    (comp (ref "U13")
      (value "AMS1117-3.3")
      (footprint "easyedapro:SOT-223-4_L6.5-W3.5-P2.30-LS7.0-BR")
      (description "输出类型:固定;最大输入电压:12V;输出电压:3.3V;最大输出电流:1A;电源纹波抑制比(PSRR):60dB@(120Hz);输出极性:正极;")
      (fields (field (name "Manufacturer") "UMW(友台半导体)"))
      (libsource (lib "easyedapro") (part "AMS1117-3.3_C347222"))
    )
    (comp (ref "U14")
      (value "CMB100N03B")
      (footprint "easyedapro:TO-263-2_L10.1-W9.1-P5.08-LS15.2-BR")
      (description "类型:N沟道;漏源电压(Vdss):30V;连续漏极电流(Id):100A;功率(Pd):300W;导通电阻(RDS(on)@Vgs,Id):4.5mΩ;")
      (fields (field (name "Manufacturer") "Cmos(广东场效应半导体)"))
      (libsource (lib "easyedapro") (part "CMB100N03B"))
    )
    (comp (ref "U15")
      (value "CMB100N03B")
      (footprint "easyedapro:TO-263-2_L10.1-W9.1-P5.08-LS15.2-BR")
      (description "类型:N沟道;漏源电压(Vdss):30V;连续漏极电流(Id):100A;功率(Pd):300W;导通电阻(RDS(on)@Vgs,Id):4.5mΩ;")
      (fields (field (name "Manufacturer") "Cmos(广东场效应半导体)"))
      (libsource (lib "easyedapro") (part "CMB100N03B"))
    )
    (comp (ref "U16")
      (value "EG2131")
      (footprint "easyedapro:SOIC-8_L5.0-W4.0-P1.27-LS6.0-BL")
      (fields (field (name "Manufacturer") "EG(屹晶微)"))
      (libsource (lib "easyedapro") (part "EG2131"))
    )
    (comp (ref "U17")
      (value "CMB100N03B")
      (footprint "easyedapro:TO-263-2_L10.1-W9.1-P5.08-LS15.2-BR")
      (description "类型:N沟道;漏源电压(Vdss):30V;连续漏极电流(Id):100A;功率(Pd):300W;导通电阻(RDS(on)@Vgs,Id):4.5mΩ;")
      (fields (field (name "Manufacturer") "Cmos(广东场效应半导体)"))
      (libsource (lib "easyedapro") (part "CMB100N03B"))
    )
    (comp (ref "U18")
      (value "CMB100N03B")
      (footprint "easyedapro:TO-263-2_L10.1-W9.1-P5.08-LS15.2-BR")
      (description "类型:N沟道;漏源电压(Vdss):30V;连续漏极电流(Id):100A;功率(Pd):300W;导通电阻(RDS(on)@Vgs,Id):4.5mΩ;")
      (fields (field (name "Manufacturer") "Cmos(广东场效应半导体)"))
      (libsource (lib "easyedapro") (part "CMB100N03B"))
    )
    (comp (ref "U19")
      (value "EG2131")
      (footprint "easyedapro:SOIC-8_L5.0-W4.0-P1.27-LS6.0-BL")
      (fields (field (name "Manufacturer") "EG(屹晶微)"))
      (libsource (lib "easyedapro") (part "EG2131"))
    )
    (comp (ref "U20")
      (value "LMV358ARZ")
      (footprint "easyedapro:SOP-8_L4.9-W3.9-P1.27-LS6.0-BL")
      (description "放大器数:双路;")
      (fields (field (name "Manufacturer") "HTCSEMI(海天芯)"))
      (libsource (lib "easyedapro") (part "LMV358ARZ"))
    )
  )
  (nets
    (net (code "1") (name "+3.3V") (class "Default")
      (node (ref "C1") (pin "2") (pinfunction "2_2") (pintype "unspecified"))
      (node (ref "C13") (pin "2") (pinfunction "2_2") (pintype "unspecified"))
      (node (ref "C3") (pin "1") (pinfunction "1_1") (pintype "unspecified"))
      (node (ref "H7") (pin "1") (pinfunction "1_1") (pintype "unspecified"))
      (node (ref "R24") (pin "1") (pinfunction "1_1") (pintype "input"))
      (node (ref "R25") (pin "1") (pinfunction "1_1") (pintype "input"))
      (node (ref "U1") (pin "1") (pinfunction "VDD_1") (pintype "unspecified"))
      (node (ref "U1") (pin "24") (pinfunction "VDD_24") (pintype "unspecified"))
      (node (ref "U1") (pin "48") (pinfunction "VDD_48") (pintype "unspecified"))
      (node (ref "U13") (pin "2") (pinfunction "VOUT(TAB)_2") (pintype "unspecified"))
      (node (ref "U13") (pin "4") (pinfunction "TAB_4") (pintype "unspecified"))
    )
    (net (code "2") (name "+3.3VA") (class "Default")
      (node (ref "C2") (pin "2") (pinfunction "2_2") (pintype "unspecified"))
      (node (ref "C22") (pin "2") (pinfunction "2_2") (pintype "unspecified"))
      (node (ref "C23") (pin "2") (pinfunction "2_2") (pintype "input"))
      (node (ref "R24") (pin "2") (pinfunction "2_2") (pintype "input"))
      (node (ref "R25") (pin "2") (pinfunction "2_2") (pintype "input"))
      (node (ref "R26") (pin "2") (pinfunction "2_2") (pintype "input"))
      (node (ref "R27") (pin "2") (pinfunction "2_2") (pintype "input"))
      (node (ref "R28") (pin "2") (pinfunction "2_2") (pintype "input"))
      (node (ref "U1") (pin "9") (pinfunction "VDDA_9") (pintype "unspecified"))
      (node (ref "U20") (pin "8") (pinfunction "VCC_8") (pintype "unspecified"))
    )
    (net (code "3") (name "+5V") (class "Default")
      (node (ref "C11") (pin "2") (pinfunction "2_2") (pintype "input"))
      (node (ref "C12") (pin "2") (pinfunction "2_2") (pintype "input"))
      (node (ref "C9") (pin "1") (pinfunction "1_1") (pintype "input"))
      (node (ref "R10") (pin "1") (pinfunction "1_1") (pintype "unspecified"))
      (node (ref "R9") (pin "1") (pinfunction "1_1") (pintype "unspecified"))
      (node (ref "U10") (pin "6") (pinfunction "VCC_6") (pintype "unspecified"))
      (node (ref "U11") (pin "4") (pinfunction "Feedback_4") (pintype "unspecified"))
      (node (ref "U12") (pin "2") (pinfunction "2_2") (pintype "unspecified"))
      (node (ref "U13") (pin "1") (pinfunction "ADJ(GND)_1") (pintype "unspecified"))
    )
    (net (code "4") (name "+15V") (class "Default")
      (node (ref "C16") (pin "2") (pinfunction "2_2") (pintype "input"))
      (node (ref "C19") (pin "2") (pinfunction "2_2") (pintype "input"))
      (node (ref "C21") (pin "1") (pinfunction "1_1") (pintype "input"))
      (node (ref "C7") (pin "2") (pinfunction "2_2") (pintype "input"))
      (node (ref "D1") (pin "1") (pinfunction "A_1") (pintype "unspecified"))
      (node (ref "D3") (pin "1") (pinfunction "K_1") (pintype "unspecified"))
      (node (ref "D4") (pin "1") (pinfunction "A_1") (pintype "unspecified"))
      (node (ref "D5") (pin "1") (pinfunction "A_1") (pintype "unspecified"))
      (node (ref "R11") (pin "2") (pinfunction "2_2") (pintype "input"))
      (node (ref "U16") (pin "1") (pinfunction "VCC_1") (pintype "unspecified"))
      (node (ref "U19") (pin "1") (pinfunction "VCC_1") (pintype "unspecified"))
      (node (ref "U9") (pin "1") (pinfunction "VCC_1") (pintype "unspecified"))
    )
    (net (code "5") (name "GND") (class "Default")
      (node (ref "C1") (pin "1") (pinfunction "1_1") (pintype "unspecified"))
      (node (ref "C10") (pin "2") (pinfunction "2_2") (pintype "input"))
      (node (ref "C11") (pin "1") (pinfunction "1_1") (pintype "input"))
      (node (ref "C12") (pin "1") (pinfunction "1_1") (pintype "input"))
      (node (ref "C13") (pin "1") (pinfunction "1_1") (pintype "unspecified"))
      (node (ref "C14") (pin "2") (pinfunction "2_2") (pintype "input"))
      (node (ref "C16") (pin "1") (pinfunction "1_1") (pintype "input"))
      (node (ref "C17") (pin "2") (pinfunction "2_2") (pintype "input"))
      (node (ref "C19") (pin "1") (pinfunction "1_1") (pintype "input"))
      (node (ref "C2") (pin "1") (pinfunction "1_1") (pintype "unspecified"))
      (node (ref "C20") (pin "2") (pinfunction "2_2") (pintype "input"))
      (node (ref "C21") (pin "2") (pinfunction "2_2") (pintype "input"))
      (node (ref "C22") (pin "1") (pinfunction "1_1") (pintype "unspecified"))
      (node (ref "C23") (pin "1") (pinfunction "1_1") (pintype "input"))
      (node (ref "C3") (pin "2") (pinfunction "2_2") (pintype "unspecified"))
      (node (ref "C4") (pin "1") (pinfunction "1_1") (pintype "input"))
      (node (ref "C5") (pin "2") (pinfunction "2_2") (pintype "input"))
      (node (ref "C7") (pin "1") (pinfunction "1_1") (pintype "input"))
      (node (ref "C8") (pin "2") (pinfunction "2_2") (pintype "input"))
      (node (ref "C9") (pin "2") (pinfunction "2_2") (pintype "input"))
      (node (ref "D2") (pin "2") (pinfunction "A_2") (pintype "unspecified"))
      (node (ref "R1") (pin "1") (pinfunction "1_1") (pintype "input"))
      (node (ref "R13") (pin "1") (pinfunction "1_1") (pintype "input"))
      (node (ref "R18") (pin "1") (pinfunction "1_1") (pintype "input"))
      (node (ref "R19") (pin "2") (pinfunction "2_2") (pintype "unspecified"))
      (node (ref "R20") (pin "1") (pinfunction "1_1") (pintype "input"))
      (node (ref "R23") (pin "1") (pinfunction "1_1") (pintype "unspecified"))
      (node (ref "R29") (pin "1") (pinfunction "1_1") (pintype "input"))
      (node (ref "SW1") (pin "1") (pinfunction "1_1") (pintype "input"))
      (node (ref "SW1") (pin "2") (pinfunction "2_2") (pintype "input"))
      (node (ref "SW2") (pin "1") (pinfunction "1_1") (pintype "input"))
      (node (ref "SW2") (pin "2") (pinfunction "2_2") (pintype "input"))
      (node (ref "SW3") (pin "1") (pinfunction "1_1") (pintype "input"))
      (node (ref "SW3") (pin "2") (pinfunction "2_2") (pintype "input"))
      (node (ref "SW4") (pin "1") (pinfunction "1_1") (pintype "input"))
      (node (ref "SW4") (pin "2") (pinfunction "2_2") (pintype "input"))
      (node (ref "U1") (pin "23") (pinfunction "VSS_23") (pintype "unspecified"))
      (node (ref "U1") (pin "47") (pinfunction "VSS_47") (pintype "unspecified"))
      (node (ref "U1") (pin "8") (pinfunction "VSSA_8") (pintype "unspecified"))
      (node (ref "U10") (pin "2") (pinfunction "SE_2") (pintype "unspecified"))
      (node (ref "U10") (pin "4") (pinfunction "GND_4") (pintype "unspecified"))
      (node (ref "U11") (pin "3") (pinfunction "GND_3") (pintype "unspecified"))
      (node (ref "U11") (pin "5") (pinfunction "ON/OFF_5") (pintype "unspecified"))
      (node (ref "U11") (pin "6") (pinfunction "GND_6") (pintype "unspecified"))
      (node (ref "U13") (pin "3") (pinfunction "VIN_3") (pintype "unspecified"))
      (node (ref "U15") (pin "3") (pinfunction "S_3") (pintype "input"))
      (node (ref "U16") (pin "4") (pinfunction "GND_4") (pintype "unspecified"))
      (node (ref "U18") (pin "3") (pinfunction "S_3") (pintype "input"))
      (node (ref "U19") (pin "4") (pinfunction "GND_4") (pintype "unspecified"))
      (node (ref "U2") (pin "2") (pinfunction "S_2") (pintype "unspecified"))
      (node (ref "U20") (pin "4") (pinfunction "GND_4") (pintype "unspecified"))
      (node (ref "U4") (pin "3") (pinfunction "S_3") (pintype "input"))
      (node (ref "U9") (pin "4") (pinfunction "GND_4") (pintype "unspecified"))
      (node (ref "X1") (pin "2") (pinfunction "2_2") (pintype "input"))
      (node (ref "X1") (pin "4") (pinfunction "4_4") (pintype "input"))
    )
    (net (code "6") (name "GND_DC-") (class "Default")
      (node (ref "R19") (pin "1") (pinfunction "1_1") (pintype "unspecified"))
      (node (ref "R21") (pin "1") (pinfunction "1_1") (pintype "input"))
    )
    (net (code "7") (name "Net-(D1-K)") (class "Default")
      (node (ref "C6") (pin "2") (pinfunction "2_2") (pintype "unspecified"))
      (node (ref "D1") (pin "2") (pinfunction "K_2") (pintype "unspecified"))
      (node (ref "U9") (pin "8") (pinfunction "VB_8") (pintype "unspecified"))
    )
    (net (code "8") (name "Net-(D2-K)") (class "Default")
      (node (ref "D2") (pin "1") (pinfunction "K_1") (pintype "unspecified"))
      (node (ref "U11") (pin "2") (pinfunction "Output_2") (pintype "unspecified"))
      (node (ref "U12") (pin "1") (pinfunction "1_1") (pintype "unspecified"))
    )
    (net (code "9") (name "Net-(D3-A)") (class "Default")
      (node (ref "D3") (pin "2") (pinfunction "A_2") (pintype "unspecified"))
      (node (ref "L2") (pin "2") (pinfunction "2_2") (pintype "unspecified"))
      (node (ref "U10") (pin "1") (pinfunction "SC_1") (pintype "unspecified"))
    )
    (net (code "10") (name "Net-(D4-K)") (class "Default")
      (node (ref "C15") (pin "2") (pinfunction "2_2") (pintype "unspecified"))
      (node (ref "D4") (pin "2") (pinfunction "K_2") (pintype "unspecified"))
      (node (ref "U16") (pin "8") (pinfunction "VB_8") (pintype "unspecified"))
    )
    (net (code "11") (name "Net-(D5-K)") (class "Default")
      (node (ref "C18") (pin "2") (pinfunction "2_2") (pintype "unspecified"))
      (node (ref "D5") (pin "2") (pinfunction "K_2") (pintype "unspecified"))
      (node (ref "U19") (pin "8") (pinfunction "VB_8") (pintype "unspecified"))
    )
    (net (code "12") (name "Net-(L1-Pad2)") (class "Default")
      (node (ref "L1") (pin "2") (pinfunction "2_2") (pintype "unspecified"))
      (node (ref "L2") (pin "1") (pinfunction "1_1") (pintype "unspecified"))
    )
    (net (code "13") (name "Net-(R2-Pad2)") (class "Default")
      (node (ref "R2") (pin "2") (pinfunction "2_2") (pintype "input"))
      (node (ref "SW1") (pin "3") (pinfunction "3_3") (pintype "input"))
      (node (ref "SW1") (pin "4") (pinfunction "4_4") (pintype "input"))
    )
    (net (code "14") (name "Net-(R3-Pad2)") (class "Default")
      (node (ref "R3") (pin "2") (pinfunction "2_2") (pintype "input"))
      (node (ref "SW2") (pin "3") (pinfunction "3_3") (pintype "input"))
      (node (ref "SW2") (pin "4") (pinfunction "4_4") (pintype "input"))
    )
    (net (code "15") (name "Net-(R4-Pad2)") (class "Default")
      (node (ref "R4") (pin "2") (pinfunction "2_2") (pintype "input"))
      (node (ref "SW3") (pin "3") (pinfunction "3_3") (pintype "input"))
      (node (ref "SW3") (pin "4") (pinfunction "4_4") (pintype "input"))
    )
    (net (code "16") (name "Net-(R5-Pad2)") (class "Default")
      (node (ref "R5") (pin "2") (pinfunction "2_2") (pintype "input"))
      (node (ref "SW4") (pin "3") (pinfunction "3_3") (pintype "input"))
      (node (ref "SW4") (pin "4") (pinfunction "4_4") (pintype "input"))
    )
    (net (code "17") (name "Net-(U1-BOOT0)") (class "Default")
      (node (ref "R1") (pin "2") (pinfunction "2_2") (pintype "input"))
      (node (ref "U1") (pin "44") (pinfunction "BOOT0_44") (pintype "unspecified"))
    )
    (net (code "18") (name "Net-(U1-PB6)") (class "Default")
      (node (ref "R5") (pin "1") (pinfunction "1_1") (pintype "input"))
      (node (ref "U1") (pin "42") (pinfunction "PB6_42") (pintype "unspecified"))
    )
    (net (code "19") (name "Net-(U1-PB7)") (class "Default")
      (node (ref "R4") (pin "1") (pinfunction "1_1") (pintype "input"))
      (node (ref "U1") (pin "43") (pinfunction "PB7_43") (pintype "unspecified"))
    )
    (net (code "20") (name "Net-(U1-PB8)") (class "Default")
      (node (ref "R3") (pin "1") (pinfunction "1_1") (pintype "input"))
      (node (ref "U1") (pin "45") (pinfunction "PB8_45") (pintype "unspecified"))
    )
    (net (code "21") (name "Net-(U1-PB9)") (class "Default")
      (node (ref "R2") (pin "1") (pinfunction "1_1") (pintype "input"))
      (node (ref "U1") (pin "46") (pinfunction "PB9_46") (pintype "unspecified"))
    )
    (net (code "22") (name "Net-(U1-PF0-OSC_IN)") (class "Default")
      (node (ref "C4") (pin "2") (pinfunction "2_2") (pintype "input"))
      (node (ref "U1") (pin "5") (pinfunction "PF0-OSC_IN_5") (pintype "unspecified"))
      (node (ref "X1") (pin "3") (pinfunction "3_3") (pintype "input"))
    )
    (net (code "23") (name "Net-(U1-PF1-OSC_OUT)") (class "Default")
      (node (ref "C5") (pin "1") (pinfunction "1_1") (pintype "input"))
      (node (ref "U1") (pin "6") (pinfunction "PF1-OSC_OUT_6") (pintype "unspecified"))
      (node (ref "X1") (pin "1") (pinfunction "1_1") (pintype "input"))
    )
    (net (code "24") (name "Net-(U2-D)") (class "Default")
      (node (ref "H8") (pin "1") (pinfunction "1_1") (pintype "unspecified"))
      (node (ref "U2") (pin "3") (pinfunction "D_3") (pintype "unspecified"))
    )
    (net (code "25") (name "Net-(U3-G)") (class "Default")
      (node (ref "R7") (pin "2") (pinfunction "2_2") (pintype "input"))
      (node (ref "U3") (pin "1") (pinfunction "G_1") (pintype "input"))
    )
    (net (code "26") (name "Net-(U3-S)") (class "Default")
      (node (ref "C6") (pin "1") (pinfunction "1_1") (pintype "unspecified"))
      (node (ref "TP2") (pin "1") (pinfunction "1_1") (pintype "input"))
      (node (ref "U3") (pin "3") (pinfunction "S_3") (pintype "input"))
      (node (ref "U4") (pin "2") (pinfunction "D_2") (pintype "input"))
      (node (ref "U9") (pin "6") (pinfunction "VS_6") (pintype "unspecified"))
    )
    (net (code "27") (name "Net-(U4-G)") (class "Default")
      (node (ref "R6") (pin "2") (pinfunction "2_2") (pintype "input"))
      (node (ref "U4") (pin "1") (pinfunction "G_1") (pintype "input"))
    )
    (net (code "28") (name "Net-(U9-HO)") (class "Default")
      (node (ref "R7") (pin "1") (pinfunction "1_1") (pintype "input"))
      (node (ref "U9") (pin "7") (pinfunction "HO_7") (pintype "unspecified"))
    )
    (net (code "29") (name "Net-(U9-LO)") (class "Default")
      (node (ref "R6") (pin "1") (pinfunction "1_1") (pintype "input"))
      (node (ref "U9") (pin "5") (pinfunction "LO_5") (pintype "unspecified"))
    )
    (net (code "30") (name "Net-(U10-CT)") (class "Default")
      (node (ref "C10") (pin "1") (pinfunction "1_1") (pintype "input"))
      (node (ref "U10") (pin "3") (pinfunction "CT_3") (pintype "unspecified"))
    )
    (net (code "31") (name "Net-(U10-DC)") (class "Default")
      (node (ref "R8") (pin "1") (pinfunction "1_1") (pintype "input"))
      (node (ref "U10") (pin "8") (pinfunction "DC_8") (pintype "unspecified"))
    )
    (net (code "32") (name "Net-(U10-FB)") (class "Default")
      (node (ref "R11") (pin "1") (pinfunction "1_1") (pintype "input"))
      (node (ref "R13") (pin "2") (pinfunction "2_2") (pintype "input"))
      (node (ref "R18") (pin "2") (pinfunction "2_2") (pintype "input"))
      (node (ref "U10") (pin "5") (pinfunction "FB_5") (pintype "unspecified"))
    )
    (net (code "33") (name "Net-(U10-IPK)") (class "Default")
      (node (ref "L1") (pin "1") (pinfunction "1_1") (pintype "unspecified"))
      (node (ref "R10") (pin "2") (pinfunction "2_2") (pintype "unspecified"))
      (node (ref "R8") (pin "2") (pinfunction "2_2") (pintype "input"))
      (node (ref "R9") (pin "2") (pinfunction "2_2") (pintype "unspecified"))
      (node (ref "U10") (pin "7") (pinfunction "IPK_7") (pintype "unspecified"))
    )
    (net (code "34") (name "Net-(U14-G)") (class "Default")
      (node (ref "R15") (pin "2") (pinfunction "2_2") (pintype "input"))
      (node (ref "U14") (pin "1") (pinfunction "G_1") (pintype "input"))
    )
    (net (code "35") (name "Net-(U14-S)") (class "Default")
      (node (ref "C15") (pin "1") (pinfunction "1_1") (pintype "unspecified"))
      (node (ref "TP3") (pin "1") (pinfunction "1_1") (pintype "input"))
      (node (ref "U14") (pin "3") (pinfunction "S_3") (pintype "input"))
      (node (ref "U15") (pin "2") (pinfunction "D_2") (pintype "input"))
      (node (ref "U16") (pin "6") (pinfunction "VS_6") (pintype "unspecified"))
    )
    (net (code "36") (name "Net-(U15-G)") (class "Default")
      (node (ref "R14") (pin "2") (pinfunction "2_2") (pintype "input"))
      (node (ref "U15") (pin "1") (pinfunction "G_1") (pintype "input"))
    )
    (net (code "37") (name "Net-(U16-HO)") (class "Default")
      (node (ref "R15") (pin "1") (pinfunction "1_1") (pintype "input"))
      (node (ref "U16") (pin "7") (pinfunction "HO_7") (pintype "unspecified"))
    )
    (net (code "38") (name "Net-(U16-LO)") (class "Default")
      (node (ref "R14") (pin "1") (pinfunction "1_1") (pintype "input"))
      (node (ref "U16") (pin "5") (pinfunction "LO_5") (pintype "unspecified"))
    )
    (net (code "39") (name "Net-(U17-G)") (class "Default")
      (node (ref "R17") (pin "2") (pinfunction "2_2") (pintype "input"))
      (node (ref "U17") (pin "1") (pinfunction "G_1") (pintype "input"))
    )
    (net (code "40") (name "Net-(U17-S)") (class "Default")
      (node (ref "C18") (pin "1") (pinfunction "1_1") (pintype "unspecified"))
      (node (ref "TP1") (pin "1") (pinfunction "1_1") (pintype "input"))
      (node (ref "U17") (pin "3") (pinfunction "S_3") (pintype "input"))
      (node (ref "U18") (pin "2") (pinfunction "D_2") (pintype "input"))
      (node (ref "U19") (pin "6") (pinfunction "VS_6") (pintype "unspecified"))
    )
    (net (code "41") (name "Net-(U18-G)") (class "Default")
      (node (ref "R16") (pin "2") (pinfunction "2_2") (pintype "input"))
      (node (ref "U18") (pin "1") (pinfunction "G_1") (pintype "input"))
    )
    (net (code "42") (name "Net-(U19-HO)") (class "Default")
      (node (ref "R17") (pin "1") (pinfunction "1_1") (pintype "input"))
      (node (ref "U19") (pin "7") (pinfunction "HO_7") (pintype "unspecified"))
    )
    (net (code "43") (name "Net-(U19-LO)") (class "Default")
      (node (ref "R16") (pin "1") (pinfunction "1_1") (pintype "input"))
      (node (ref "U19") (pin "5") (pinfunction "LO_5") (pintype "unspecified"))
    )
    (net (code "44") (name "Net-(U20A-IN1+)") (class "Default")
      (node (ref "R22") (pin "2") (pinfunction "2_2") (pintype "unspecified"))
      (node (ref "U20") (pin "3") (pinfunction "IN1+_3") (pintype "unspecified"))
      (node (ref "U20") (pin "7") (pinfunction "OUT2_7") (pintype "output"))
    )
    (net (code "45") (name "Net-(U20A-IN1-)") (class "Default")
      (node (ref "R26") (pin "1") (pinfunction "1_1") (pintype "input"))
      (node (ref "R27") (pin "1") (pinfunction "1_1") (pintype "input"))
      (node (ref "R28") (pin "1") (pinfunction "1_1") (pintype "input"))
      (node (ref "R29") (pin "2") (pinfunction "2_2") (pintype "input"))
      (node (ref "U20") (pin "2") (pinfunction "IN1-_2") (pintype "unspecified"))
    )
    (net (code "46") (name "Net-(U20A-OUT)") (class "Default")
      (node (ref "R30") (pin "1") (pinfunction "1_1") (pintype "input"))
      (node (ref "U20") (pin "1") (pinfunction "OUT_1") (pintype "output"))
    )
    (net (code "47") (name "Net-(U20B-IN2+)") (class "Default")
      (node (ref "R20") (pin "2") (pinfunction "2_2") (pintype "input"))
      (node (ref "R23") (pin "2") (pinfunction "2_2") (pintype "unspecified"))
      (node (ref "U20") (pin "5") (pinfunction "IN2+_5") (pintype "unspecified"))
    )
    (net (code "48") (name "Net-(U20B-IN2-)") (class "Default")
      (node (ref "R21") (pin "2") (pinfunction "2_2") (pintype "input"))
      (node (ref "R22") (pin "1") (pinfunction "1_1") (pintype "unspecified"))
      (node (ref "U20") (pin "6") (pinfunction "IN2-_6") (pintype "unspecified"))
    )
    (net (code "49") (name "PA0_XUAN_BIAN_TIAO0") (class "Default")
      (node (ref "H3") (pin "1") (pinfunction "1_1") (pintype "unspecified"))
    )
    (net (code "50") (name "PA1_SPI2_MOSI") (class "Default")
      (node (ref "H4") (pin "1") (pinfunction "1_1") (pintype "unspecified"))
    )
    (net (code "51") (name "PA2_SPI2_SCK") (class "Default")
      (node (ref "H5") (pin "1") (pinfunction "1_1") (pintype "unspecified"))
    )
    (net (code "52") (name "PA3_SPI2_CS") (class "Default")
      (node (ref "H6") (pin "1") (pinfunction "1_1") (pintype "unspecified"))
    )
    (net (code "53") (name "PA8_ATIM_CH1A_U_H") (class "Default")
      (node (ref "U1") (pin "29") (pinfunction "PA8_29") (pintype "unspecified"))
      (node (ref "U9") (pin "2") (pinfunction "HIN_2") (pintype "unspecified"))
    )
    (net (code "54") (name "PA9_ATIM_CH2A_U_H") (class "Default")
      (node (ref "U16") (pin "2") (pinfunction "HIN_2") (pintype "unspecified"))
    )
    (net (code "55") (name "PA9_ATIM_CH2A_V_H") (class "Default")
      (node (ref "U1") (pin "30") (pinfunction "PA9_30") (pintype "unspecified"))
    )
    (net (code "56") (name "PA10_ATIM_CH3A_U_H") (class "Default")
      (node (ref "U19") (pin "2") (pinfunction "HIN_2") (pintype "unspecified"))
    )
    (net (code "57") (name "PA10_ATIM_CH3A_W_H") (class "Default")
      (node (ref "U1") (pin "31") (pinfunction "PA10_31") (pintype "unspecified"))
    )
    (net (code "58") (name "PA13_SWDIO") (class "Default")
      (node (ref "H2") (pin "1") (pinfunction "1_1") (pintype "unspecified"))
      (node (ref "U1") (pin "34") (pinfunction "PA13_34") (pintype "unspecified"))
    )
    (net (code "59") (name "PA14_SWCLK") (class "Default")
      (node (ref "H1") (pin "1") (pinfunction "1_1") (pintype "unspecified"))
      (node (ref "U1") (pin "37") (pinfunction "PA14_37") (pintype "unspecified"))
    )
    (net (code "60") (name "PA15_SPI1_CS_LCD_A0") (class "Default")
      (node (ref "U1") (pin "38") (pinfunction "PA15_38") (pintype "unspecified"))
    )
    (net (code "61") (name "PB3_SPI1_SCK") (class "Default")
      (node (ref "U1") (pin "39") (pinfunction "PB3_39") (pintype "unspecified"))
    )
    (net (code "62") (name "PB4_LCD_RST") (class "Default")
      (node (ref "U1") (pin "40") (pinfunction "PB4_40") (pintype "unspecified"))
    )
    (net (code "63") (name "PB5_SPI1_MOSI") (class "Default")
      (node (ref "U1") (pin "41") (pinfunction "PB5_41") (pintype "unspecified"))
    )
    (net (code "64") (name "PB12_ATIM_BK") (class "Default")
      (node (ref "R30") (pin "2") (pinfunction "2_2") (pintype "input"))
      (node (ref "U1") (pin "25") (pinfunction "PB12_25") (pintype "unspecified"))
    )
    (net (code "65") (name "PB13_ATIM_CH1B_U_L") (class "Default")
      (node (ref "U1") (pin "26") (pinfunction "PB13_26") (pintype "unspecified"))
      (node (ref "U9") (pin "3") (pinfunction "LIN_3") (pintype "unspecified"))
    )
    (net (code "66") (name "PB14_ATIM_CH2B_U_L") (class "Default")
      (node (ref "U16") (pin "3") (pinfunction "LIN_3") (pintype "unspecified"))
    )
    (net (code "67") (name "PB14_ATIM_CH2B_V_L") (class "Default")
      (node (ref "U1") (pin "27") (pinfunction "PB14_27") (pintype "unspecified"))
    )
    (net (code "68") (name "PB15_ATIM_CH3B_U_L") (class "Default")
      (node (ref "U19") (pin "3") (pinfunction "LIN_3") (pintype "unspecified"))
    )
    (net (code "69") (name "PB15_ATIM_CH3B_W_L") (class "Default")
      (node (ref "U1") (pin "28") (pinfunction "PB15_28") (pintype "unspecified"))
    )
    (net (code "70") (name "VCC") (class "Default")
      (node (ref "C14") (pin "1") (pinfunction "1_1") (pintype "input"))
      (node (ref "C17") (pin "1") (pinfunction "1_1") (pintype "input"))
      (node (ref "C20") (pin "1") (pinfunction "1_1") (pintype "input"))
      (node (ref "C8") (pin "1") (pinfunction "1_1") (pintype "input"))
      (node (ref "U11") (pin "1") (pinfunction "Vin_1") (pintype "unspecified"))
      (node (ref "U14") (pin "2") (pinfunction "D_2") (pintype "input"))
      (node (ref "U17") (pin "2") (pinfunction "D_2") (pintype "input"))
      (node (ref "U3") (pin "2") (pinfunction "D_2") (pintype "input"))
    )
    (net (code "72") (name "unconnected-(U1-NRST-Pad7)") (class "Default")
      (node (ref "U1") (pin "7") (pinfunction "NRST_7") (pintype "unspecified"))
    )
    (net (code "73") (name "unconnected-(U1-PA0-Pad10)") (class "Default")
      (node (ref "U1") (pin "10") (pinfunction "PA0_10") (pintype "unspecified"))
    )
    (net (code "74") (name "unconnected-(U1-PA1-Pad11)") (class "Default")
      (node (ref "U1") (pin "11") (pinfunction "PA1_11") (pintype "unspecified"))
    )
    (net (code "75") (name "unconnected-(U1-PA2-Pad12)") (class "Default")
      (node (ref "U1") (pin "12") (pinfunction "PA2_12") (pintype "unspecified"))
    )
    (net (code "76") (name "unconnected-(U1-PA3-Pad13)") (class "Default")
      (node (ref "U1") (pin "13") (pinfunction "PA3_13") (pintype "unspecified"))
    )
    (net (code "77") (name "unconnected-(U1-PA4-Pad14)") (class "Default")
      (node (ref "U1") (pin "14") (pinfunction "PA4_14") (pintype "unspecified"))
    )
    (net (code "78") (name "unconnected-(U1-PA5-Pad15)") (class "Default")
      (node (ref "U1") (pin "15") (pinfunction "PA5_15") (pintype "unspecified"))
    )
    (net (code "79") (name "unconnected-(U1-PA6-Pad16)") (class "Default")
      (node (ref "U1") (pin "16") (pinfunction "PA6_16") (pintype "unspecified"))
    )
    (net (code "80") (name "unconnected-(U1-PA7-Pad17)") (class "Default")
      (node (ref "U1") (pin "17") (pinfunction "PA7_17") (pintype "unspecified"))
    )
    (net (code "81") (name "unconnected-(U1-PA11-Pad32)") (class "Default")
      (node (ref "U1") (pin "32") (pinfunction "PA11_32") (pintype "unspecified"))
    )
    (net (code "82") (name "unconnected-(U1-PA12-Pad33)") (class "Default")
      (node (ref "U1") (pin "33") (pinfunction "PA12_33") (pintype "unspecified"))
    )
    (net (code "83") (name "unconnected-(U1-PB0-Pad18)") (class "Default")
      (node (ref "U1") (pin "18") (pinfunction "PB0_18") (pintype "unspecified"))
    )
    (net (code "84") (name "unconnected-(U1-PB1-Pad19)") (class "Default")
      (node (ref "U1") (pin "19") (pinfunction "PB1_19") (pintype "unspecified"))
    )
    (net (code "85") (name "unconnected-(U1-PB2-Pad20)") (class "Default")
      (node (ref "U1") (pin "20") (pinfunction "PB2_20") (pintype "unspecified"))
    )
    (net (code "86") (name "unconnected-(U1-PB10-Pad21)") (class "Default")
      (node (ref "U1") (pin "21") (pinfunction "PB10_21") (pintype "unspecified"))
    )
    (net (code "87") (name "unconnected-(U1-PB11-Pad22)") (class "Default")
      (node (ref "U1") (pin "22") (pinfunction "PB11_22") (pintype "unspecified"))
    )
    (net (code "88") (name "unconnected-(U1-PC13-Pad2)") (class "Default")
      (node (ref "U1") (pin "2") (pinfunction "PC13_2") (pintype "unspecified"))
    )
    (net (code "89") (name "unconnected-(U1-PC14-OSC32_IN-Pad3)") (class "Default")
      (node (ref "U1") (pin "3") (pinfunction "PC14-OSC32_IN_3") (pintype "unspecified"))
    )
    (net (code "90") (name "unconnected-(U1-PC15-OSC32_OUT-Pad4)") (class "Default")
      (node (ref "U1") (pin "4") (pinfunction "PC15-OSC32_OUT_4") (pintype "unspecified"))
    )
    (net (code "91") (name "unconnected-(U1-PF6-Pad35)") (class "Default")
      (node (ref "U1") (pin "35") (pinfunction "PF6_35") (pintype "unspecified"))
    )
    (net (code "92") (name "unconnected-(U1-PF7-Pad36)") (class "Default")
      (node (ref "U1") (pin "36") (pinfunction "PF7_36") (pintype "unspecified"))
    )
    (net (code "93") (name "unconnected-(U2-G-Pad1)") (class "Default")
      (node (ref "U2") (pin "1") (pinfunction "G_1") (pintype "unspecified"))
    )
  )
)
